# SK-PiCo.net
KiCad netlist of a schematic drawn in Altium Designer
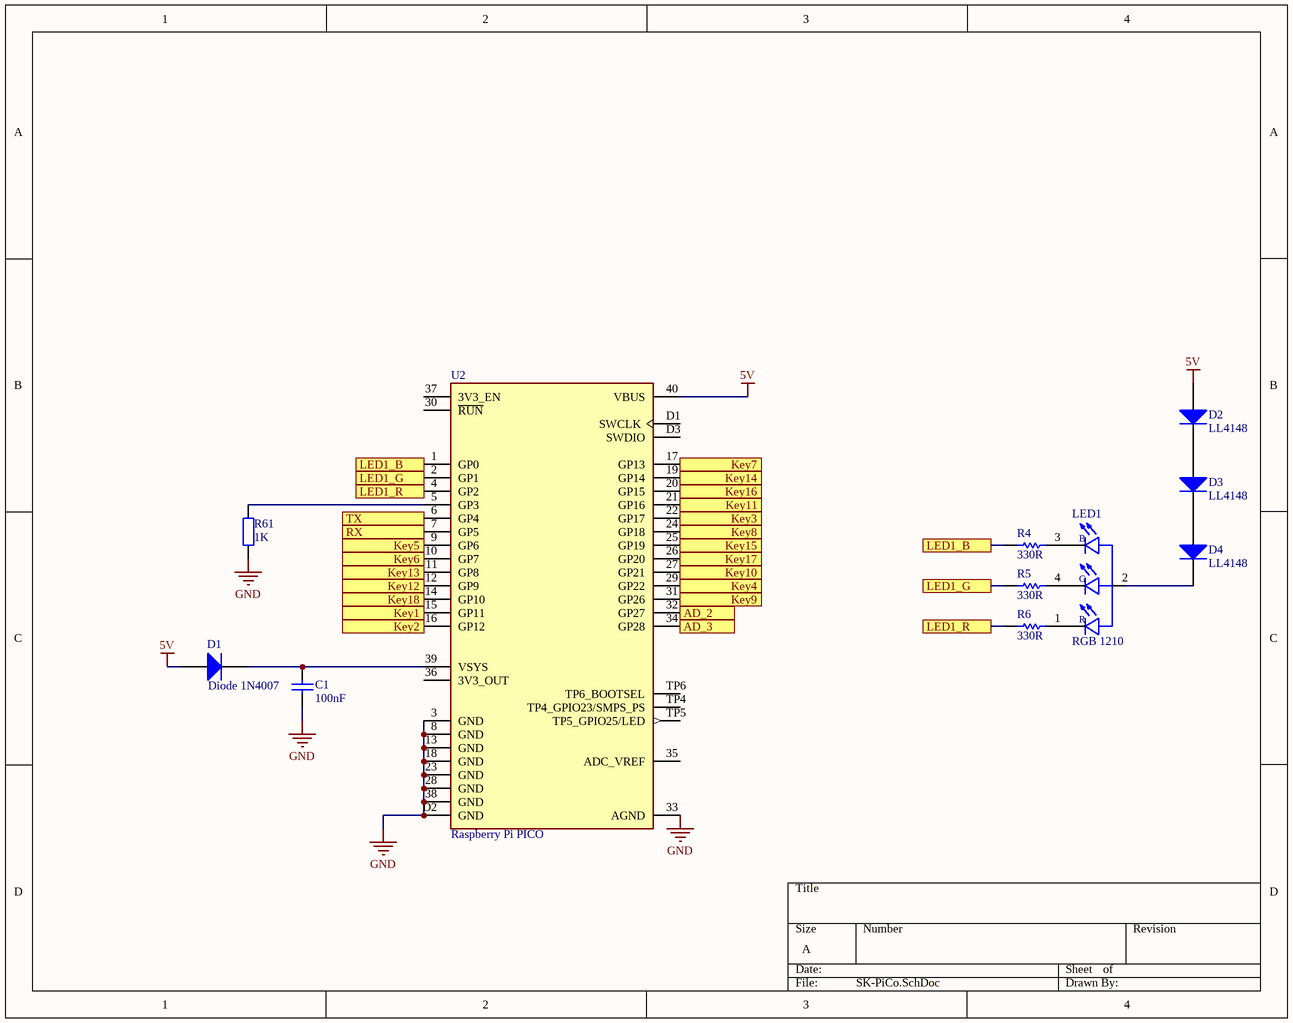
[diagram p0: SK-PiCo.SchDoc]

(export (version "E")
  (design (tool "Eeschema 10.0.6"))
  (components
    (comp (ref "C1")
      (value "100nF")
      (footprint "SMH_RES0805-STD")
      (description "Capacitor")
      (fields (field (name "PUBLISHER") "Altium Limited"))
      (libsource (lib "Miscellaneous Devices") (part "Cap"))
    )
    (comp (ref "D1")
      (value "Diode 1N4007")
      (footprint "SMH_SMA")
      (description "1 Amp General Purpose Rectifier")
      (fields (field (name "PUBLISHER") "Altium Limited"))
      (libsource (lib "Miscellaneous Devices") (part "Diode 1N4007"))
    )
    (comp (ref "D2")
      (value "LL4148")
      (footprint "SMH_MINIMELF")
      (description "1 Amp General Purpose Rectifier")
      (fields (field (name "PUBLISHER") "Altium Limited"))
      (libsource (lib "Miscellaneous Devices") (part "Diode 1N4004"))
    )
    (comp (ref "D3")
      (value "LL4148")
      (footprint "SMH_MINIMELF")
      (description "1 Amp General Purpose Rectifier")
      (fields (field (name "PUBLISHER") "Altium Limited"))
      (libsource (lib "Miscellaneous Devices") (part "Diode 1N4004"))
    )
    (comp (ref "D4")
      (value "LL4148")
      (footprint "SMH_MINIMELF")
      (description "1 Amp General Purpose Rectifier")
      (fields (field (name "PUBLISHER") "Altium Limited"))
      (libsource (lib "Miscellaneous Devices") (part "Diode 1N4004"))
    )
    (comp (ref "LED1")
      (value "RGB 1210")
      (footprint "SMH_LED_1210-RGB")
      (libsource (lib "Mlib") (part "LED RGB"))
    )
    (comp (ref "R4")
      (value "330R")
      (footprint "SMH_1206STD")
      (description "Resistor")
      (fields (field (name "PUBLISHER") "Altium Limited"))
      (libsource (lib "Miscellaneous Devices") (part "Res1"))
    )
    (comp (ref "R5")
      (value "330R")
      (footprint "SMH_1206STD")
      (description "Resistor")
      (fields (field (name "PUBLISHER") "Altium Limited"))
      (libsource (lib "Miscellaneous Devices") (part "Res1"))
    )
    (comp (ref "R6")
      (value "330R")
      (footprint "SMH_1206STD")
      (description "Resistor")
      (fields (field (name "PUBLISHER") "Altium Limited"))
      (libsource (lib "Miscellaneous Devices") (part "Res1"))
    )
    (comp (ref "R61")
      (value "1K")
      (footprint "SMH_RES0805-STD")
      (description "Resistor")
      (fields (field (name "PUBLISHER") "Altium Limited"))
      (libsource (lib "Miscellaneous Devices") (part "Res2"))
    )
    (comp (ref "U2")
      (value "Raspberry Pi PICO")
      (footprint "SMH_PicoPi")
      (libsource (lib "Mlib") (part "PICO Pi"))
    )
  )
  (nets
    (net (code "1") (name "/AD_2") (class "Default")
      (node (ref "U2") (pin "32") (pinfunction "GP27_32") (pintype "open_collector"))
    )
    (net (code "2") (name "/AD_3") (class "Default")
      (node (ref "U2") (pin "34") (pinfunction "GP28_34") (pintype "open_collector"))
    )
    (net (code "3") (name "/Key1") (class "Default")
      (node (ref "U2") (pin "15") (pinfunction "GP11_15") (pintype "open_collector"))
    )
    (net (code "4") (name "/Key2") (class "Default")
      (node (ref "U2") (pin "16") (pinfunction "GP12_16") (pintype "open_collector"))
    )
    (net (code "5") (name "/Key3") (class "Default")
      (node (ref "U2") (pin "22") (pinfunction "GP17_22") (pintype "open_collector"))
    )
    (net (code "6") (name "/Key4") (class "Default")
      (node (ref "U2") (pin "29") (pinfunction "GP22_29") (pintype "open_collector"))
    )
    (net (code "7") (name "/Key5") (class "Default")
      (node (ref "U2") (pin "9") (pinfunction "GP6_9") (pintype "open_collector"))
    )
    (net (code "8") (name "/Key6") (class "Default")
      (node (ref "U2") (pin "10") (pinfunction "GP7_10") (pintype "open_collector"))
    )
    (net (code "9") (name "/Key7") (class "Default")
      (node (ref "U2") (pin "17") (pinfunction "GP13_17") (pintype "open_collector"))
    )
    (net (code "10") (name "/Key8") (class "Default")
      (node (ref "U2") (pin "24") (pinfunction "GP18_24") (pintype "open_collector"))
    )
    (net (code "11") (name "/Key9") (class "Default")
      (node (ref "U2") (pin "31") (pinfunction "GP26_31") (pintype "open_collector"))
    )
    (net (code "12") (name "/Key10") (class "Default")
      (node (ref "U2") (pin "27") (pinfunction "GP21_27") (pintype "open_collector"))
    )
    (net (code "13") (name "/Key11") (class "Default")
      (node (ref "U2") (pin "21") (pinfunction "GP16_21") (pintype "open_collector"))
    )
    (net (code "14") (name "/Key12") (class "Default")
      (node (ref "U2") (pin "12") (pinfunction "GP9_12") (pintype "open_collector"))
    )
    (net (code "15") (name "/Key13") (class "Default")
      (node (ref "U2") (pin "11") (pinfunction "GP8_11") (pintype "open_collector"))
    )
    (net (code "16") (name "/Key14") (class "Default")
      (node (ref "U2") (pin "19") (pinfunction "GP14_19") (pintype "open_collector"))
    )
    (net (code "17") (name "/Key15") (class "Default")
      (node (ref "U2") (pin "25") (pinfunction "GP19_25") (pintype "open_collector"))
    )
    (net (code "18") (name "/Key16") (class "Default")
      (node (ref "U2") (pin "20") (pinfunction "GP15_20") (pintype "open_collector"))
    )
    (net (code "19") (name "/Key17") (class "Default")
      (node (ref "U2") (pin "26") (pinfunction "GP20_26") (pintype "open_collector"))
    )
    (net (code "20") (name "/Key18") (class "Default")
      (node (ref "U2") (pin "14") (pinfunction "GP10_14") (pintype "open_collector"))
    )
    (net (code "21") (name "/LED1_B") (class "Default")
      (node (ref "R4") (pin "2") (pinfunction "2_2") (pintype "passive"))
      (node (ref "U2") (pin "1") (pinfunction "GP0_1") (pintype "open_collector"))
    )
    (net (code "22") (name "/LED1_G") (class "Default")
      (node (ref "R5") (pin "2") (pinfunction "2_2") (pintype "passive"))
      (node (ref "U2") (pin "2") (pinfunction "GP1_2") (pintype "open_collector"))
    )
    (net (code "23") (name "/LED1_R") (class "Default")
      (node (ref "R6") (pin "2") (pinfunction "2_2") (pintype "passive"))
      (node (ref "U2") (pin "4") (pinfunction "GP2_4") (pintype "open_collector"))
    )
    (net (code "24") (name "/RX") (class "Default")
      (node (ref "U2") (pin "7") (pinfunction "GP5_7") (pintype "open_collector"))
    )
    (net (code "25") (name "/TX") (class "Default")
      (node (ref "U2") (pin "6") (pinfunction "GP4_6") (pintype "open_collector"))
    )
    (net (code "26") (name "5V") (class "Default")
      (node (ref "D1") (pin "1") (pinfunction "A_1") (pintype "passive"))
      (node (ref "D2") (pin "1") (pinfunction "A_1") (pintype "passive"))
      (node (ref "U2") (pin "40") (pinfunction "VBUS_40") (pintype "power_in"))
    )
    (net (code "27") (name "GND") (class "Default")
      (node (ref "C1") (pin "2") (pinfunction "2_2") (pintype "passive"))
      (node (ref "R61") (pin "2") (pinfunction "2_2") (pintype "passive"))
      (node (ref "U2") (pin "13") (pinfunction "GND_13") (pintype "power_in"))
      (node (ref "U2") (pin "18") (pinfunction "GND_18") (pintype "power_in"))
      (node (ref "U2") (pin "23") (pinfunction "GND_23") (pintype "power_in"))
      (node (ref "U2") (pin "28") (pinfunction "GND_28") (pintype "power_in"))
      (node (ref "U2") (pin "3") (pinfunction "GND_3") (pintype "power_in"))
      (node (ref "U2") (pin "33") (pinfunction "AGND_33") (pintype "power_in"))
      (node (ref "U2") (pin "38") (pinfunction "GND_38") (pintype "power_in"))
      (node (ref "U2") (pin "8") (pinfunction "GND_8") (pintype "power_in"))
      (node (ref "U2") (pin "D2") (pinfunction "GND_D2") (pintype "power_in"))
    )
    (net (code "28") (name "Net-(D1-K)") (class "Default")
      (node (ref "C1") (pin "1") (pinfunction "1_1") (pintype "passive"))
      (node (ref "D1") (pin "2") (pinfunction "K_2") (pintype "passive"))
      (node (ref "U2") (pin "39") (pinfunction "VSYS_39") (pintype "power_in"))
    )
    (net (code "29") (name "Net-(D2-K)") (class "Default")
      (node (ref "D2") (pin "2") (pinfunction "K_2") (pintype "passive"))
      (node (ref "D3") (pin "1") (pinfunction "A_1") (pintype "passive"))
    )
    (net (code "30") (name "Net-(D3-K)") (class "Default")
      (node (ref "D3") (pin "2") (pinfunction "K_2") (pintype "passive"))
      (node (ref "D4") (pin "1") (pinfunction "A_1") (pintype "passive"))
    )
    (net (code "31") (name "Net-(D4-K)") (class "Default")
      (node (ref "D4") (pin "2") (pinfunction "K_2") (pintype "passive"))
      (node (ref "LED1") (pin "2") (pinfunction "Anode_2") (pintype "passive"))
    )
    (net (code "32") (name "Net-(LED1-B)") (class "Default")
      (node (ref "LED1") (pin "3") (pinfunction "B_3") (pintype "passive"))
      (node (ref "R4") (pin "1") (pinfunction "1_1") (pintype "passive"))
    )
    (net (code "33") (name "Net-(LED1-G)") (class "Default")
      (node (ref "LED1") (pin "4") (pinfunction "G_4") (pintype "passive"))
      (node (ref "R5") (pin "1") (pinfunction "1_1") (pintype "passive"))
    )
    (net (code "34") (name "Net-(LED1-R)") (class "Default")
      (node (ref "LED1") (pin "1") (pinfunction "R_1") (pintype "passive"))
      (node (ref "R6") (pin "1") (pinfunction "1_1") (pintype "passive"))
    )
    (net (code "35") (name "Net-(U2-GP3)") (class "Default")
      (node (ref "R61") (pin "1") (pinfunction "1_1") (pintype "passive"))
      (node (ref "U2") (pin "5") (pinfunction "GP3_5") (pintype "open_collector"))
    )
    (net (code "36") (name "unconnected-(U2-3V3_EN-Pad37)") (class "Default")
      (node (ref "U2") (pin "37") (pinfunction "3V3_EN_37") (pintype "open_collector"))
    )
    (net (code "37") (name "unconnected-(U2-3V3_OUT-Pad36)") (class "Default")
      (node (ref "U2") (pin "36") (pinfunction "3V3_OUT_36") (pintype "power_in"))
    )
    (net (code "38") (name "unconnected-(U2-ADC_VREF-Pad35)") (class "Default")
      (node (ref "U2") (pin "35") (pinfunction "ADC_VREF_35") (pintype "power_in"))
    )
    (net (code "39") (name "unconnected-(U2-SWCLK-PadD1)") (class "Default")
      (node (ref "U2") (pin "D1") (pinfunction "SWCLK_D1") (pintype "open_collector"))
    )
    (net (code "40") (name "unconnected-(U2-SWDIO-PadD3)") (class "Default")
      (node (ref "U2") (pin "D3") (pinfunction "SWDIO_D3") (pintype "open_collector"))
    )
    (net (code "41") (name "unconnected-(U2-TP4_GPIO23{slash}SMPS_PS-PadTP4)") (class "Default")
      (node (ref "U2") (pin "TP4") (pinfunction "TP4_GPIO23/SMPS_PS_TP4") (pintype "passive"))
    )
    (net (code "42") (name "unconnected-(U2-TP5_GPIO25{slash}LED-PadTP5)") (class "Default")
      (node (ref "U2") (pin "TP5") (pinfunction "TP5_GPIO25/LED_TP5") (pintype "output"))
    )
    (net (code "43") (name "unconnected-(U2-TP6_BOOTSEL-PadTP6)") (class "Default")
      (node (ref "U2") (pin "TP6") (pinfunction "TP6_BOOTSEL_TP6") (pintype "open_collector"))
    )
    (net (code "44") (name "unconnected-(U2-~{RUN}-Pad30)") (class "Default")
      (node (ref "U2") (pin "30") (pinfunction "~{RUN}_30") (pintype "open_collector"))
    )
  )
)
